# easyeda_schematic.net
KiCad netlist of a schematic drawn in EasyEDA
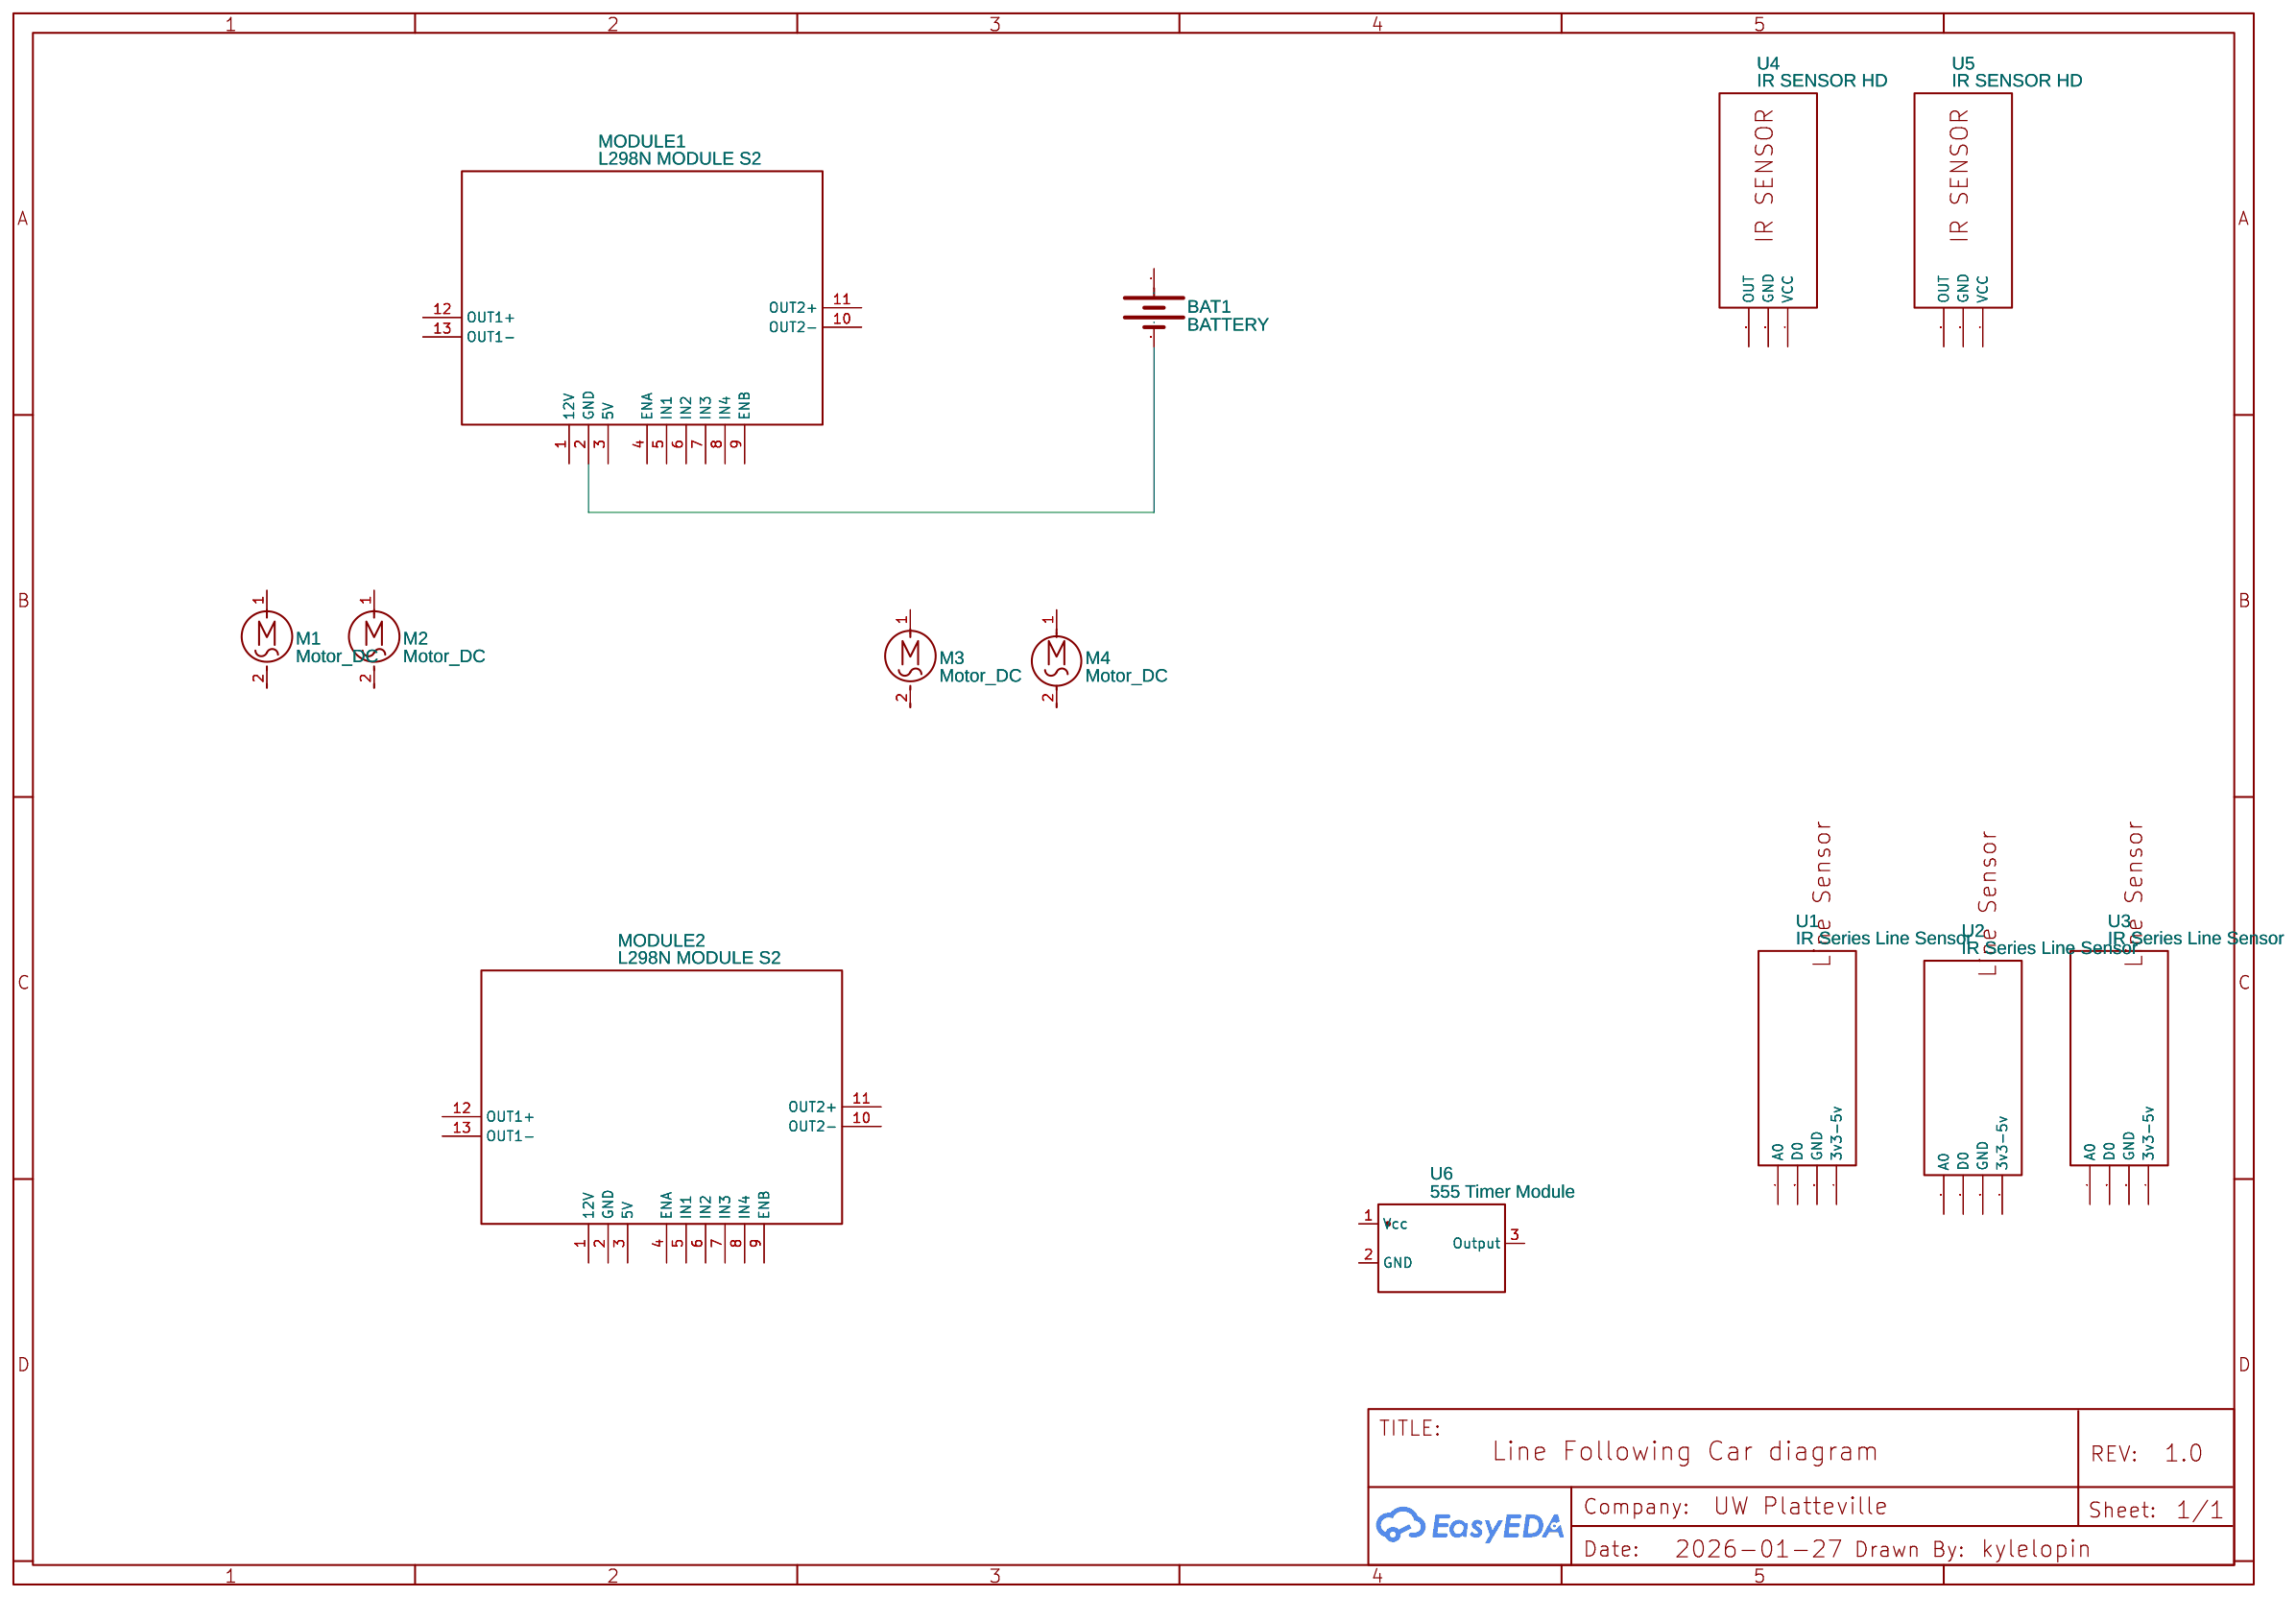
[diagram p0: schematic sheet]

(export (version "E")
  (design (tool "Eeschema 10.0.6"))
  (components
    (comp (ref "BAT1") (value "BATTERY") (libsource (lib "") (part "BATTERY")))
    (comp (ref "M1") (value "Motor_DC") (libsource (lib "") (part "Motor_AC")))
    (comp (ref "M2") (value "Motor_DC") (libsource (lib "") (part "Motor_AC")))
    (comp (ref "M3") (value "Motor_DC") (libsource (lib "") (part "Motor_AC")))
    (comp (ref "M4") (value "Motor_DC") (libsource (lib "") (part "Motor_AC_1")))
    (comp (ref "MODULE1") (value "L298N MODULE S2") (libsource (lib "") (part "L298N MODULE S2")))
    (comp (ref "MODULE2") (value "L298N MODULE S2") (libsource (lib "") (part "L298N MODULE S2")))
    (comp (ref "U1")
      (value "IR Series Line Sensor")
      (libsource (lib "") (part "MH-Sensor-Series Line Sensor_1"))
    )
    (comp (ref "U2")
      (value "IR Series Line Sensor")
      (libsource (lib "") (part "MH-Sensor-Series Line Sensor_1"))
    )
    (comp (ref "U3")
      (value "IR Series Line Sensor")
      (libsource (lib "") (part "MH-Sensor-Series Line Sensor_1"))
    )
    (comp (ref "U4") (value "IR SENSOR HD") (libsource (lib "") (part "MH-Sensor-Series Line Sensor")))
    (comp (ref "U5") (value "IR SENSOR HD") (libsource (lib "") (part "MH-Sensor-Series Line Sensor")))
    (comp (ref "U6") (value "555 Timer Module") (libsource (lib "") (part "555 Timer Module")))
  )
  (nets
    (net (code "1") (name "Net-(BAT1--)") (class "Default")
      (node (ref "BAT1") (pin "2") (pinfunction "-_2") (pintype "passive"))
      (node (ref "MODULE1") (pin "2") (pinfunction "GND_2") (pintype "passive"))
    )
    (net (code "2") (name "unconnected-(BAT1-+-Pad1)") (class "Default")
      (node (ref "BAT1") (pin "1") (pinfunction "+_1") (pintype "passive"))
    )
    (net (code "3") (name "unconnected-(M1-Pad1)") (class "Default")
      (node (ref "M1") (pin "1") (pintype "unspecified"))
    )
    (net (code "4") (name "unconnected-(M1-Pad2)") (class "Default")
      (node (ref "M1") (pin "2") (pintype "unspecified"))
    )
    (net (code "5") (name "unconnected-(M2-Pad1)") (class "Default")
      (node (ref "M2") (pin "1") (pintype "unspecified"))
    )
    (net (code "6") (name "unconnected-(M2-Pad2)") (class "Default")
      (node (ref "M2") (pin "2") (pintype "unspecified"))
    )
    (net (code "7") (name "unconnected-(M3-Pad1)") (class "Default")
      (node (ref "M3") (pin "1") (pintype "unspecified"))
    )
    (net (code "8") (name "unconnected-(M3-Pad2)") (class "Default")
      (node (ref "M3") (pin "2") (pintype "unspecified"))
    )
    (net (code "9") (name "unconnected-(M4-Pad1)") (class "Default")
      (node (ref "M4") (pin "1") (pintype "unspecified"))
    )
    (net (code "10") (name "unconnected-(M4-Pad2)") (class "Default")
      (node (ref "M4") (pin "2") (pintype "unspecified"))
    )
    (net (code "11") (name "unconnected-(MODULE1-5V-Pad3)") (class "Default")
      (node (ref "MODULE1") (pin "3") (pinfunction "5V_3") (pintype "passive"))
    )
    (net (code "12") (name "unconnected-(MODULE1-12V-Pad1)") (class "Default")
      (node (ref "MODULE1") (pin "1") (pinfunction "12V_1") (pintype "passive"))
    )
    (net (code "13") (name "unconnected-(MODULE1-ENA-Pad4)") (class "Default")
      (node (ref "MODULE1") (pin "4") (pinfunction "ENA_4") (pintype "input"))
    )
    (net (code "14") (name "unconnected-(MODULE1-ENB-Pad9)") (class "Default")
      (node (ref "MODULE1") (pin "9") (pinfunction "ENB_9") (pintype "input"))
    )
    (net (code "15") (name "unconnected-(MODULE1-IN1-Pad5)") (class "Default")
      (node (ref "MODULE1") (pin "5") (pinfunction "IN1_5") (pintype "input"))
    )
    (net (code "16") (name "unconnected-(MODULE1-IN2-Pad6)") (class "Default")
      (node (ref "MODULE1") (pin "6") (pinfunction "IN2_6") (pintype "input"))
    )
    (net (code "17") (name "unconnected-(MODULE1-IN3-Pad7)") (class "Default")
      (node (ref "MODULE1") (pin "7") (pinfunction "IN3_7") (pintype "input"))
    )
    (net (code "18") (name "unconnected-(MODULE1-IN4-Pad8)") (class "Default")
      (node (ref "MODULE1") (pin "8") (pinfunction "IN4_8") (pintype "input"))
    )
    (net (code "19") (name "unconnected-(MODULE1-OUT1+-Pad12)") (class "Default")
      (node (ref "MODULE1") (pin "12") (pinfunction "OUT1+_12") (pintype "output"))
    )
    (net (code "20") (name "unconnected-(MODULE1-OUT1--Pad13)") (class "Default")
      (node (ref "MODULE1") (pin "13") (pinfunction "OUT1-_13") (pintype "output"))
    )
    (net (code "21") (name "unconnected-(MODULE1-OUT2+-Pad11)") (class "Default")
      (node (ref "MODULE1") (pin "11") (pinfunction "OUT2+_11") (pintype "output"))
    )
    (net (code "22") (name "unconnected-(MODULE1-OUT2--Pad10)") (class "Default")
      (node (ref "MODULE1") (pin "10") (pinfunction "OUT2-_10") (pintype "output"))
    )
    (net (code "23") (name "unconnected-(MODULE2-5V-Pad3)") (class "Default")
      (node (ref "MODULE2") (pin "3") (pinfunction "5V_3") (pintype "passive"))
    )
    (net (code "24") (name "unconnected-(MODULE2-12V-Pad1)") (class "Default")
      (node (ref "MODULE2") (pin "1") (pinfunction "12V_1") (pintype "passive"))
    )
    (net (code "25") (name "unconnected-(MODULE2-ENA-Pad4)") (class "Default")
      (node (ref "MODULE2") (pin "4") (pinfunction "ENA_4") (pintype "input"))
    )
    (net (code "26") (name "unconnected-(MODULE2-ENB-Pad9)") (class "Default")
      (node (ref "MODULE2") (pin "9") (pinfunction "ENB_9") (pintype "input"))
    )
    (net (code "27") (name "unconnected-(MODULE2-GND-Pad2)") (class "Default")
      (node (ref "MODULE2") (pin "2") (pinfunction "GND_2") (pintype "passive"))
    )
    (net (code "28") (name "unconnected-(MODULE2-IN1-Pad5)") (class "Default")
      (node (ref "MODULE2") (pin "5") (pinfunction "IN1_5") (pintype "input"))
    )
    (net (code "29") (name "unconnected-(MODULE2-IN2-Pad6)") (class "Default")
      (node (ref "MODULE2") (pin "6") (pinfunction "IN2_6") (pintype "input"))
    )
    (net (code "30") (name "unconnected-(MODULE2-IN3-Pad7)") (class "Default")
      (node (ref "MODULE2") (pin "7") (pinfunction "IN3_7") (pintype "input"))
    )
    (net (code "31") (name "unconnected-(MODULE2-IN4-Pad8)") (class "Default")
      (node (ref "MODULE2") (pin "8") (pinfunction "IN4_8") (pintype "input"))
    )
    (net (code "32") (name "unconnected-(MODULE2-OUT1+-Pad12)") (class "Default")
      (node (ref "MODULE2") (pin "12") (pinfunction "OUT1+_12") (pintype "output"))
    )
    (net (code "33") (name "unconnected-(MODULE2-OUT1--Pad13)") (class "Default")
      (node (ref "MODULE2") (pin "13") (pinfunction "OUT1-_13") (pintype "output"))
    )
    (net (code "34") (name "unconnected-(MODULE2-OUT2+-Pad11)") (class "Default")
      (node (ref "MODULE2") (pin "11") (pinfunction "OUT2+_11") (pintype "output"))
    )
    (net (code "35") (name "unconnected-(MODULE2-OUT2--Pad10)") (class "Default")
      (node (ref "MODULE2") (pin "10") (pinfunction "OUT2-_10") (pintype "output"))
    )
    (net (code "36") (name "unconnected-(U1-3v3-5v-Pad4)") (class "Default")
      (node (ref "U1") (pin "4") (pinfunction "3v3-5v_4") (pintype "unspecified"))
    )
    (net (code "37") (name "unconnected-(U1-A0-Pad1)") (class "Default")
      (node (ref "U1") (pin "1") (pinfunction "A0_1") (pintype "unspecified"))
    )
    (net (code "38") (name "unconnected-(U1-D0-Pad2)") (class "Default")
      (node (ref "U1") (pin "2") (pinfunction "D0_2") (pintype "unspecified"))
    )
    (net (code "39") (name "unconnected-(U1-GND-Pad3)") (class "Default")
      (node (ref "U1") (pin "3") (pinfunction "GND_3") (pintype "unspecified"))
    )
    (net (code "40") (name "unconnected-(U2-3v3-5v-Pad4)") (class "Default")
      (node (ref "U2") (pin "4") (pinfunction "3v3-5v_4") (pintype "unspecified"))
    )
    (net (code "41") (name "unconnected-(U2-A0-Pad1)") (class "Default")
      (node (ref "U2") (pin "1") (pinfunction "A0_1") (pintype "unspecified"))
    )
    (net (code "42") (name "unconnected-(U2-D0-Pad2)") (class "Default")
      (node (ref "U2") (pin "2") (pinfunction "D0_2") (pintype "unspecified"))
    )
    (net (code "43") (name "unconnected-(U2-GND-Pad3)") (class "Default")
      (node (ref "U2") (pin "3") (pinfunction "GND_3") (pintype "unspecified"))
    )
    (net (code "44") (name "unconnected-(U3-3v3-5v-Pad4)") (class "Default")
      (node (ref "U3") (pin "4") (pinfunction "3v3-5v_4") (pintype "unspecified"))
    )
    (net (code "45") (name "unconnected-(U3-A0-Pad1)") (class "Default")
      (node (ref "U3") (pin "1") (pinfunction "A0_1") (pintype "unspecified"))
    )
    (net (code "46") (name "unconnected-(U3-D0-Pad2)") (class "Default")
      (node (ref "U3") (pin "2") (pinfunction "D0_2") (pintype "unspecified"))
    )
    (net (code "47") (name "unconnected-(U3-GND-Pad3)") (class "Default")
      (node (ref "U3") (pin "3") (pinfunction "GND_3") (pintype "unspecified"))
    )
    (net (code "48") (name "unconnected-(U4-GND-Pad3)") (class "Default")
      (node (ref "U4") (pin "3") (pinfunction "GND_3") (pintype "unspecified"))
    )
    (net (code "49") (name "unconnected-(U4-OUT-Pad2)") (class "Default")
      (node (ref "U4") (pin "2") (pinfunction "OUT_2") (pintype "unspecified"))
    )
    (net (code "50") (name "unconnected-(U4-VCC-Pad4)") (class "Default")
      (node (ref "U4") (pin "4") (pinfunction "VCC_4") (pintype "unspecified"))
    )
    (net (code "51") (name "unconnected-(U5-GND-Pad3)") (class "Default")
      (node (ref "U5") (pin "3") (pinfunction "GND_3") (pintype "unspecified"))
    )
    (net (code "52") (name "unconnected-(U5-OUT-Pad2)") (class "Default")
      (node (ref "U5") (pin "2") (pinfunction "OUT_2") (pintype "unspecified"))
    )
    (net (code "53") (name "unconnected-(U5-VCC-Pad4)") (class "Default")
      (node (ref "U5") (pin "4") (pinfunction "VCC_4") (pintype "unspecified"))
    )
    (net (code "54") (name "unconnected-(U6-GND-Pad2)") (class "Default")
      (node (ref "U6") (pin "2") (pinfunction "GND_2") (pintype "unspecified"))
    )
    (net (code "55") (name "unconnected-(U6-Output-Pad3)") (class "Default")
      (node (ref "U6") (pin "3") (pinfunction "Output_3") (pintype "unspecified"))
    )
    (net (code "56") (name "unconnected-(U6-Vcc-Pad1)") (class "Default")
      (node (ref "U6") (pin "1") (pinfunction "Vcc_1") (pintype "unspecified"))
    )
  )
)
